# fet_board.net
KiCad netlist of a schematic drawn in EAGLE
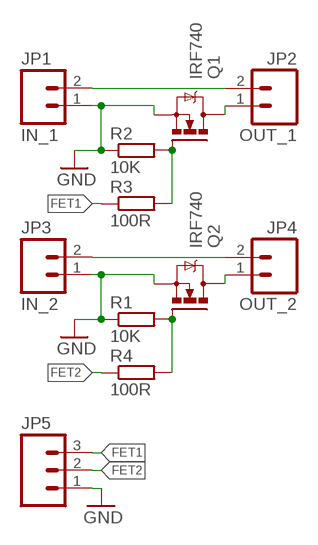
[diagram p0: schematic, sheet 1]

(export (version "E")
  (design (tool "Eeschema 10.0.6"))
  (components
    (comp (ref "JP1")
      (value "IN_1")
      (footprint "eagle-import:SCREWTERMINAL-3.5MM-2-NS")
      (libsource (lib "eagle-import") (part "M023.5MM-NO_SILK"))
    )
    (comp (ref "JP2")
      (value "OUT_1")
      (footprint "eagle-import:SCREWTERMINAL-3.5MM-2-NS")
      (libsource (lib "eagle-import") (part "M023.5MM-NO_SILK"))
    )
    (comp (ref "JP3")
      (value "IN_2")
      (footprint "eagle-import:SCREWTERMINAL-3.5MM-2-NS")
      (libsource (lib "eagle-import") (part "M023.5MM-NO_SILK"))
    )
    (comp (ref "JP4")
      (value "OUT_2")
      (footprint "eagle-import:SCREWTERMINAL-3.5MM-2-NS")
      (libsource (lib "eagle-import") (part "M023.5MM-NO_SILK"))
    )
    (comp (ref "JP5")
      (value "M03POLAR_LOCK")
      (footprint "eagle-import:MOLEX-1X3_LOCK")
      (libsource (lib "eagle-import") (part "M03POLAR_LOCK"))
    )
    (comp (ref "Q1")
      (value "IRF740")
      (footprint "eagle-import:TO220BV")
      (libsource (lib "eagle-import") (part "IRF740"))
    )
    (comp (ref "Q2")
      (value "IRF740")
      (footprint "eagle-import:TO220BV")
      (libsource (lib "eagle-import") (part "IRF740"))
    )
    (comp (ref "R1")
      (value "10K")
      (footprint "eagle-import:R0805")
      (libsource (lib "eagle-import") (part "R-EU_R0805"))
    )
    (comp (ref "R2")
      (value "10K")
      (footprint "eagle-import:R0805")
      (libsource (lib "eagle-import") (part "R-EU_R0805"))
    )
    (comp (ref "R3")
      (value "100R")
      (footprint "eagle-import:R0805")
      (libsource (lib "eagle-import") (part "R-EU_R0805"))
    )
    (comp (ref "R4")
      (value "100R")
      (footprint "eagle-import:R0805")
      (libsource (lib "eagle-import") (part "R-EU_R0805"))
    )
  )
  (nets
    (net (code "1") (name "FET1") (class "Default")
      (node (ref "JP5") (pin "3") (pinfunction "3_3") (pintype "passive"))
      (node (ref "R3") (pin "1") (pinfunction "1_1") (pintype "passive"))
    )
    (net (code "2") (name "FET2") (class "Default")
      (node (ref "JP5") (pin "2") (pinfunction "2_2") (pintype "passive"))
      (node (ref "R4") (pin "1") (pinfunction "1_1") (pintype "passive"))
    )
    (net (code "3") (name "GND") (class "Default")
      (node (ref "JP1") (pin "1") (pinfunction "1_1") (pintype "passive"))
      (node (ref "JP3") (pin "1") (pinfunction "1_1") (pintype "passive"))
      (node (ref "JP5") (pin "1") (pinfunction "1_1") (pintype "passive"))
      (node (ref "Q1") (pin "S") (pinfunction "S_S") (pintype "passive"))
      (node (ref "Q2") (pin "S") (pinfunction "S_S") (pintype "passive"))
      (node (ref "R1") (pin "1") (pinfunction "1_1") (pintype "passive"))
      (node (ref "R2") (pin "1") (pinfunction "1_1") (pintype "passive"))
    )
    (net (code "4") (name "Net-(JP1-Pad2)") (class "Default")
      (node (ref "JP1") (pin "2") (pinfunction "2_2") (pintype "passive"))
      (node (ref "JP2") (pin "2") (pinfunction "2_2") (pintype "passive"))
    )
    (net (code "5") (name "Net-(JP2-Pad1)") (class "Default")
      (node (ref "JP2") (pin "1") (pinfunction "1_1") (pintype "passive"))
      (node (ref "Q1") (pin "D") (pinfunction "D_D") (pintype "passive"))
    )
    (net (code "6") (name "Net-(JP3-Pad2)") (class "Default")
      (node (ref "JP3") (pin "2") (pinfunction "2_2") (pintype "passive"))
      (node (ref "JP4") (pin "2") (pinfunction "2_2") (pintype "passive"))
    )
    (net (code "7") (name "Net-(JP4-Pad1)") (class "Default")
      (node (ref "JP4") (pin "1") (pinfunction "1_1") (pintype "passive"))
      (node (ref "Q2") (pin "D") (pinfunction "D_D") (pintype "passive"))
    )
    (net (code "8") (name "Net-(Q1-PadG)") (class "Default")
      (node (ref "Q1") (pin "G") (pinfunction "G_G") (pintype "passive"))
      (node (ref "R2") (pin "2") (pinfunction "2_2") (pintype "passive"))
      (node (ref "R3") (pin "2") (pinfunction "2_2") (pintype "passive"))
    )
    (net (code "9") (name "Net-(Q2-PadG)") (class "Default")
      (node (ref "Q2") (pin "G") (pinfunction "G_G") (pintype "passive"))
      (node (ref "R1") (pin "2") (pinfunction "2_2") (pintype "passive"))
      (node (ref "R4") (pin "2") (pinfunction "2_2") (pintype "passive"))
    )
  )
)
